# Instruction_Register.net
KiCad netlist of a schematic drawn in Altium Designer
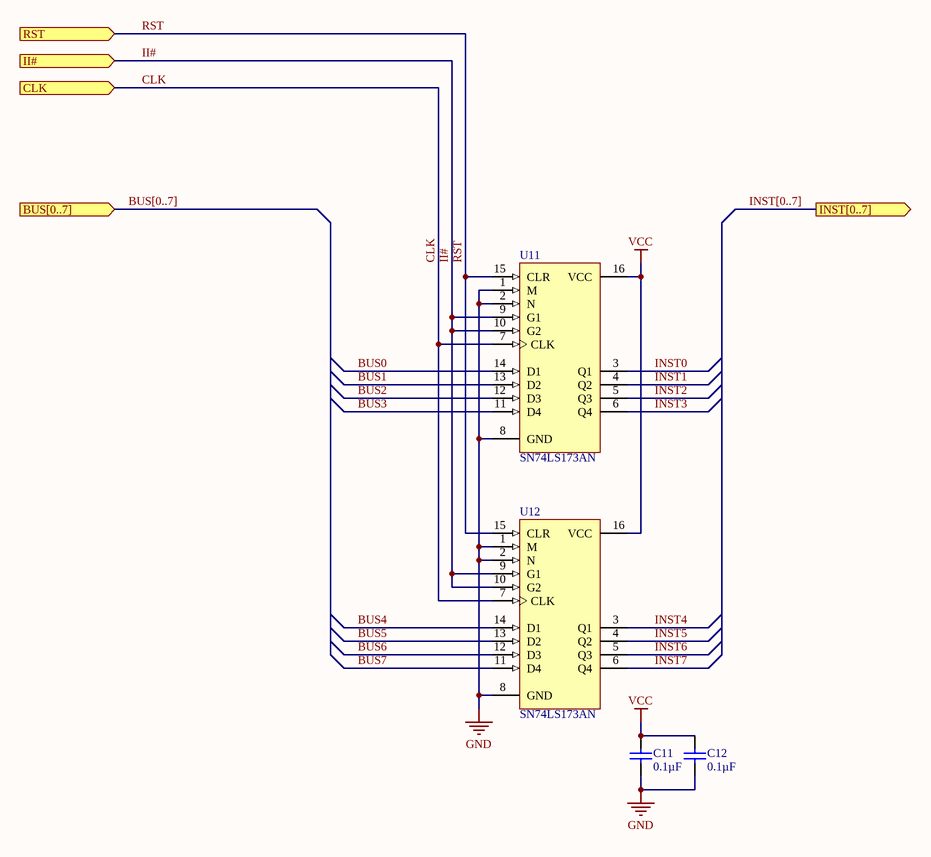
[diagram p0: Instruction Register.SchDoc]

(export (version "E")
  (design (tool "Eeschema 10.0.6"))
  (components
    (comp (ref "C11")
      (value "K104K15X7RF5TL2")
      (footprint "VISH-K104K15X7RF5TL2")
      (description "Ceramic Capacitor, 100 nF, +/- 10%, 50 V, -55 to 125 degC, 2-Pin THD, RoHS, Tape and Reel")
      (fields
        (field (name "MANUFACTURER") "Vishay")
        (field (name "TOLERANCE") "±10%")
        (field (name "CAPACITANCE") "0.1µF")
      )
      (libsource (lib "Altium Content Vault") (part "CAP-NP-2"))
    )
    (comp (ref "C12")
      (value "K104K15X7RF5TL2")
      (footprint "VISH-K104K15X7RF5TL2")
      (description "Ceramic Capacitor, 100 nF, +/- 10%, 50 V, -55 to 125 degC, 2-Pin THD, RoHS, Tape and Reel")
      (fields
        (field (name "MANUFACTURER") "Vishay")
        (field (name "TOLERANCE") "±10%")
        (field (name "CAPACITANCE") "0.1µF")
      )
      (libsource (lib "Altium Content Vault") (part "CAP-NP-2"))
    )
    (comp (ref "U11")
      (value "SN74LS173AN")
      (footprint "N016D")
      (description "4-Bit D-Type Register with 3-State Outputs")
      (fields (field (name "PUBLISHER") "Altium Limited"))
      (libsource (lib "TI Logic Flip-Flop") (part "SN74LS173AN"))
    )
    (comp (ref "U12")
      (value "SN74LS173AN")
      (footprint "N016D")
      (description "4-Bit D-Type Register with 3-State Outputs")
      (fields (field (name "PUBLISHER") "Altium Limited"))
      (libsource (lib "TI Logic Flip-Flop") (part "SN74LS173AN"))
    )
  )
  (nets
    (net (code "1") (name "/BUS0") (class "Default")
      (node (ref "U11") (pin "14") (pinfunction "D1_14") (pintype "input"))
    )
    (net (code "2") (name "/BUS1") (class "Default")
      (node (ref "U11") (pin "13") (pinfunction "D2_13") (pintype "input"))
    )
    (net (code "3") (name "/BUS2") (class "Default")
      (node (ref "U11") (pin "12") (pinfunction "D3_12") (pintype "input"))
    )
    (net (code "4") (name "/BUS3") (class "Default")
      (node (ref "U11") (pin "11") (pinfunction "D4_11") (pintype "input"))
    )
    (net (code "5") (name "/BUS4") (class "Default")
      (node (ref "U12") (pin "14") (pinfunction "D1_14") (pintype "input"))
    )
    (net (code "6") (name "/BUS5") (class "Default")
      (node (ref "U12") (pin "13") (pinfunction "D2_13") (pintype "input"))
    )
    (net (code "7") (name "/BUS6") (class "Default")
      (node (ref "U12") (pin "12") (pinfunction "D3_12") (pintype "input"))
    )
    (net (code "8") (name "/BUS7") (class "Default")
      (node (ref "U12") (pin "11") (pinfunction "D4_11") (pintype "input"))
    )
    (net (code "10") (name "/CLK") (class "Default")
      (node (ref "U11") (pin "7") (pinfunction "CLK_7") (pintype "input"))
      (node (ref "U12") (pin "7") (pinfunction "CLK_7") (pintype "input"))
    )
    (net (code "11") (name "/II#") (class "Default")
      (node (ref "U11") (pin "10") (pinfunction "G2_10") (pintype "input"))
      (node (ref "U11") (pin "9") (pinfunction "G1_9") (pintype "input"))
      (node (ref "U12") (pin "10") (pinfunction "G2_10") (pintype "input"))
      (node (ref "U12") (pin "9") (pinfunction "G1_9") (pintype "input"))
    )
    (net (code "12") (name "/INST0") (class "Default")
      (node (ref "U11") (pin "3") (pinfunction "Q1_3") (pintype "tri_state"))
    )
    (net (code "13") (name "/INST1") (class "Default")
      (node (ref "U11") (pin "4") (pinfunction "Q2_4") (pintype "tri_state"))
    )
    (net (code "14") (name "/INST2") (class "Default")
      (node (ref "U11") (pin "5") (pinfunction "Q3_5") (pintype "tri_state"))
    )
    (net (code "15") (name "/INST3") (class "Default")
      (node (ref "U11") (pin "6") (pinfunction "Q4_6") (pintype "tri_state"))
    )
    (net (code "16") (name "/INST4") (class "Default")
      (node (ref "U12") (pin "3") (pinfunction "Q1_3") (pintype "tri_state"))
    )
    (net (code "17") (name "/INST5") (class "Default")
      (node (ref "U12") (pin "4") (pinfunction "Q2_4") (pintype "tri_state"))
    )
    (net (code "18") (name "/INST6") (class "Default")
      (node (ref "U12") (pin "5") (pinfunction "Q3_5") (pintype "tri_state"))
    )
    (net (code "19") (name "/INST7") (class "Default")
      (node (ref "U12") (pin "6") (pinfunction "Q4_6") (pintype "tri_state"))
    )
    (net (code "21") (name "/RST") (class "Default")
      (node (ref "U11") (pin "15") (pinfunction "CLR_15") (pintype "input"))
      (node (ref "U12") (pin "15") (pinfunction "CLR_15") (pintype "input"))
    )
    (net (code "22") (name "GND") (class "Default")
      (node (ref "C11") (pin "2") (pinfunction "2_2") (pintype "passive"))
      (node (ref "C12") (pin "2") (pinfunction "2_2") (pintype "passive"))
      (node (ref "U11") (pin "1") (pinfunction "M_1") (pintype "input"))
      (node (ref "U11") (pin "2") (pinfunction "N_2") (pintype "input"))
      (node (ref "U11") (pin "8") (pinfunction "GND_8") (pintype "power_in"))
      (node (ref "U12") (pin "1") (pinfunction "M_1") (pintype "input"))
      (node (ref "U12") (pin "2") (pinfunction "N_2") (pintype "input"))
      (node (ref "U12") (pin "8") (pinfunction "GND_8") (pintype "power_in"))
    )
    (net (code "23") (name "VCC") (class "Default")
      (node (ref "C11") (pin "1") (pinfunction "1_1") (pintype "passive"))
      (node (ref "C12") (pin "1") (pinfunction "1_1") (pintype "passive"))
      (node (ref "U11") (pin "16") (pinfunction "VCC_16") (pintype "power_in"))
      (node (ref "U12") (pin "16") (pinfunction "VCC_16") (pintype "power_in"))
    )
  )
)
